# Boom_Deployment.net
KiCad netlist of a schematic drawn in Altium Designer
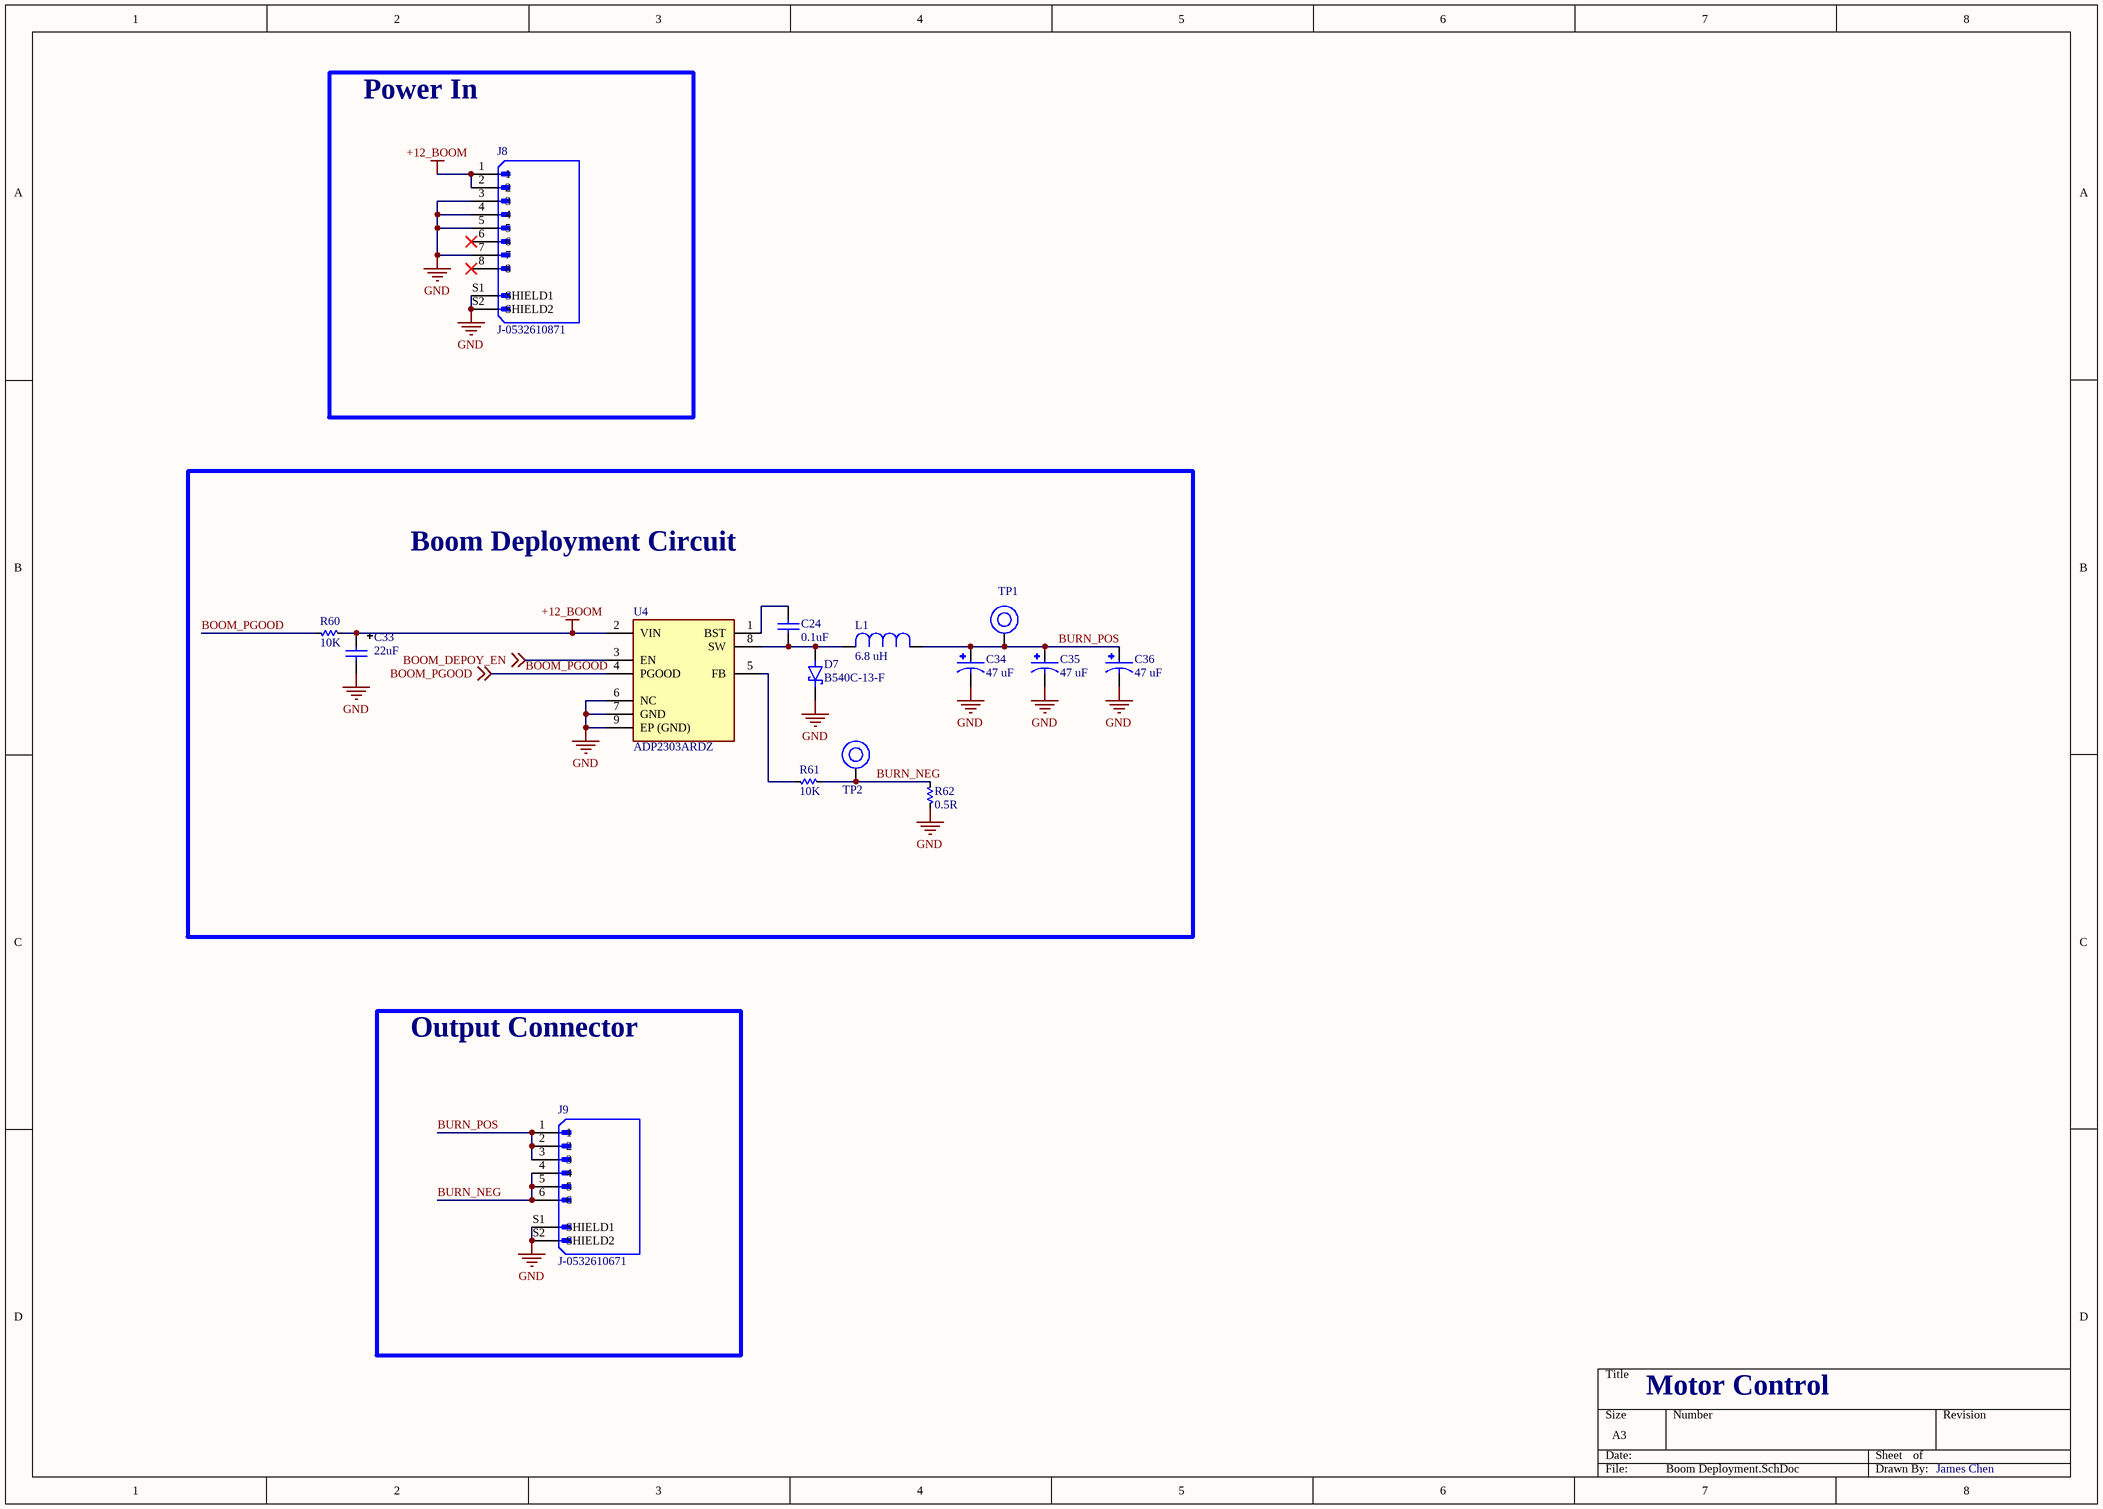
[diagram p0: Boom Deployment.SchDoc]

(export (version "E")
  (design (tool "Eeschema 10.0.6"))
  (components
    (comp (ref "C24")
      (value "0.1uF")
      (footprint "0603")
      (description "0.1 µF ±10% 25V Ceramic Capacitor X7R 0603 (1608 Metric)")
      (fields
        (field (name "DISTRIBUTOR PART #") "1276-1006-1-ND")
        (field (name "MANUFACTURER") "Samsung Electro-Mechanics")
      )
      (libsource (lib "Burn Wire Dev Board") (part "CC-104-K-25V-X7R-0603"))
    )
    (comp (ref "C33")
      (value "22uF")
      (footprint "CAP TANT 1206 (A) TCJ")
      (description "CAP TANT 22UF 10% 10V 1206")
      (fields
        (field (name "DISTRIBUTOR PART #") "478-11193-1-ND")
        (field (name "MANUFACTURER") "KYOCERA AVX")
      )
      (libsource (lib "Burn Wire Dev Board") (part "CT-225-M-20V-OTH-1206"))
    )
    (comp (ref "C34")
      (value "47 uF")
      (footprint "CC-25SVPF47M")
      (description "CAP ALUM POLY 47UF 20% 25V SMD")
      (fields
        (field (name "DISTRIBUTOR PART #") "P16513CT-ND")
        (field (name "MANUFACTURER") "Panasonic Electronic Components")
      )
      (libsource (lib "Burn Wire Dev Board") (part "CC-25SVPF47M"))
    )
    (comp (ref "C35")
      (value "47 uF")
      (footprint "CC-25SVPF47M")
      (description "CAP ALUM POLY 47UF 20% 25V SMD")
      (fields
        (field (name "DISTRIBUTOR PART #") "P16513CT-ND")
        (field (name "MANUFACTURER") "Panasonic Electronic Components")
      )
      (libsource (lib "Burn Wire Dev Board") (part "CC-25SVPF47M"))
    )
    (comp (ref "C36")
      (value "47 uF")
      (footprint "CC-25SVPF47M")
      (description "CAP ALUM POLY 47UF 20% 25V SMD")
      (fields
        (field (name "DISTRIBUTOR PART #") "P16513CT-ND")
        (field (name "MANUFACTURER") "Panasonic Electronic Components")
      )
      (libsource (lib "Burn Wire Dev Board") (part "CC-25SVPF47M"))
    )
    (comp (ref "D7")
      (value "B540C-13-F")
      (footprint "D-B540C-13-F")
      (description "DIODE SCHOTTKY 40V 5A SMC")
      (fields
        (field (name "MANUFACTURER") "Diodes Incorporated")
        (field (name "DISTRIBUTOR PART #") "B540C-FDICT-ND")
      )
      (libsource (lib "Burn Wire Dev Board") (part "D-B540C-13-F"))
    )
    (comp (ref "J8")
      (value "J-0532610871")
      (footprint "J-532610871")
      (description "CONN HEADER SMD R/A 8POS 1.25MM")
      (fields
        (field (name "MANFACTURER PART #") "0532610871")
        (field (name "DISTRIBUTOR PART #") "WM7626CT-ND")
      )
      (libsource (lib "OBC Development Board") (part "J-0532610871"))
    )
    (comp (ref "J9")
      (value "J-0532610671")
      (footprint "J-0532610671")
      (description "CONN HEADER SMD R/A 6POS 1.25MM")
      (fields
        (field (name "MANFACTURER PART #") "0532610671")
        (field (name "DISTRIBUTOR PART #") "WM7624CT-ND")
      )
      (libsource (lib "Burn Wire Dev Board") (part "J-0532610671"))
    )
    (comp (ref "L1")
      (value "6.8 uH")
      (footprint "L-IHLP4040DZER6R8M01")
      (description "FIXED IND 6.8UH 8A 23.3 MOHM SMD")
      (fields
        (field (name "MANUFACTURER") "Vishay Dale")
        (field (name "MANUFACTURER PART #") "IHLP4040DZER6R8M01")
      )
      (libsource (lib "Burn Wire Dev Board") (part "L-IHLP4040DZER6R8M01"))
    )
    (comp (ref "R60")
      (value "10K")
      (footprint "0603")
      (description "RES 10K OHM 1% 1/8W 0603")
      (fields
        (field (name "DISTRIBUTOR PART #") "RNCP0603FTD10K0CT-ND")
        (field (name "MANUFACTURER") "Stackpole Electronics Inc")
      )
      (libsource (lib "Burn Wire Dev Board") (part "RT-10K0-F-1/16W-0603"))
    )
    (comp (ref "R61")
      (value "10K")
      (footprint "0603")
      (description "RES 10K OHM 1% 1/8W 0603")
      (fields
        (field (name "DISTRIBUTOR PART #") "RNCP0603FTD10K0CT-ND")
        (field (name "MANUFACTURER") "Stackpole Electronics Inc")
      )
      (libsource (lib "Burn Wire Dev Board") (part "RT-10K0-F-1/16W-0603"))
    )
    (comp (ref "R62")
      (value "0.5R")
      (footprint "2010")
      (description "RES 0.5 OHM 1% 1W 2010")
      (fields
        (field (name "DISTRIBUTOR PART #") "541-10112-1-ND")
        (field (name "MANUFACTURER") "Vishay Dale")
      )
      (libsource (lib "Burn Wire Dev Board") (part "RT-0.5R0-F-1W-2010"))
    )
    (comp (ref "TP1")
      (value "TP")
      (footprint "TP")
      (description "Test Point")
      (libsource (lib "PowerManagmentBoard_V4.0") (part "TP"))
    )
    (comp (ref "TP2")
      (value "TP")
      (footprint "TP")
      (description "Test Point")
      (libsource (lib "PowerManagmentBoard_V4.0") (part "TP"))
    )
    (comp (ref "U4")
      (value "ADP2303ARDZ")
      (footprint "U-ADP2303ARDZ")
      (description "IC REG BUCK ADJUSTABLE 3A 8SOIC")
      (fields
        (field (name "MANUFACTURER") "Analog Devices Inc.")
        (field (name "DISTRIBUTOR PART #") "505-ADP2303ARDZ-ND")
      )
      (libsource (lib "Burn Wire Dev Board") (part "U-ADP2303ARDZ"))
    )
  )
  (nets
    (net (code "1") (name "+12_BOOM") (class "Default")
      (node (ref "C33") (pin "1") (pinfunction "1_1") (pintype "passive"))
      (node (ref "J8") (pin "1") (pinfunction "1_1") (pintype "passive"))
      (node (ref "J8") (pin "2") (pinfunction "2_2") (pintype "passive"))
      (node (ref "R60") (pin "2") (pintype "passive"))
      (node (ref "U4") (pin "2") (pinfunction "VIN_2") (pintype "passive"))
    )
    (net (code "3") (name "/BURN_NEG") (class "Default")
      (node (ref "J9") (pin "4") (pinfunction "4_4") (pintype "passive"))
      (node (ref "J9") (pin "5") (pinfunction "5_5") (pintype "passive"))
      (node (ref "J9") (pin "6") (pinfunction "6_6") (pintype "passive"))
      (node (ref "R61") (pin "2") (pintype "passive"))
      (node (ref "R62") (pin "2") (pintype "passive"))
      (node (ref "TP2") (pin "1") (pinfunction "1_1") (pintype "passive"))
    )
    (net (code "4") (name "/BURN_POS") (class "Default")
      (node (ref "C34") (pin "1") (pinfunction "1_1") (pintype "passive"))
      (node (ref "C35") (pin "1") (pinfunction "1_1") (pintype "passive"))
      (node (ref "C36") (pin "1") (pinfunction "1_1") (pintype "passive"))
      (node (ref "J9") (pin "1") (pinfunction "1_1") (pintype "passive"))
      (node (ref "J9") (pin "2") (pinfunction "2_2") (pintype "passive"))
      (node (ref "J9") (pin "3") (pinfunction "3_3") (pintype "passive"))
      (node (ref "L1") (pin "1") (pinfunction "1_1") (pintype "passive"))
      (node (ref "TP1") (pin "1") (pinfunction "1_1") (pintype "passive"))
    )
    (net (code "5") (name "BOOM_DEPOY_EN") (class "Default")
      (node (ref "U4") (pin "3") (pinfunction "EN_3") (pintype "passive"))
    )
    (net (code "6") (name "BOOM_PGOOD") (class "Default")
      (node (ref "R60") (pin "1") (pintype "passive"))
      (node (ref "U4") (pin "4") (pinfunction "PGOOD_4") (pintype "passive"))
    )
    (net (code "7") (name "GND") (class "Default")
      (node (ref "C33") (pin "2") (pinfunction "2_2") (pintype "passive"))
      (node (ref "C34") (pin "2") (pinfunction "2_2") (pintype "passive"))
      (node (ref "C35") (pin "2") (pinfunction "2_2") (pintype "passive"))
      (node (ref "C36") (pin "2") (pinfunction "2_2") (pintype "passive"))
      (node (ref "D7") (pin "C") (pinfunction "K_C") (pintype "passive"))
      (node (ref "J8") (pin "3") (pinfunction "3_3") (pintype "passive"))
      (node (ref "J8") (pin "4") (pinfunction "4_4") (pintype "passive"))
      (node (ref "J8") (pin "5") (pinfunction "5_5") (pintype "passive"))
      (node (ref "J8") (pin "7") (pinfunction "7_7") (pintype "passive"))
      (node (ref "J8") (pin "S1") (pinfunction "SHIELD1_S1") (pintype "passive"))
      (node (ref "J8") (pin "S2") (pinfunction "SHIELD2_S2") (pintype "passive"))
      (node (ref "J9") (pin "S1") (pinfunction "SHIELD1_S1") (pintype "passive"))
      (node (ref "J9") (pin "S2") (pinfunction "SHIELD2_S2") (pintype "passive"))
      (node (ref "R62") (pin "1") (pintype "passive"))
      (node (ref "U4") (pin "6") (pinfunction "NC_6") (pintype "passive"))
      (node (ref "U4") (pin "7") (pinfunction "GND_7") (pintype "passive"))
      (node (ref "U4") (pin "9") (pinfunction "EP_(GND)_9") (pintype "passive"))
    )
    (net (code "8") (name "Net-(U4-BST)") (class "Default")
      (node (ref "C24") (pin "2") (pinfunction "2_2") (pintype "passive"))
      (node (ref "U4") (pin "1") (pinfunction "BST_1") (pintype "passive"))
    )
    (net (code "9") (name "Net-(U4-FB)") (class "Default")
      (node (ref "R61") (pin "1") (pintype "passive"))
      (node (ref "U4") (pin "5") (pinfunction "FB_5") (pintype "passive"))
    )
    (net (code "10") (name "Net-(U4-SW)") (class "Default")
      (node (ref "C24") (pin "1") (pinfunction "1_1") (pintype "passive"))
      (node (ref "D7") (pin "A") (pinfunction "A_A") (pintype "passive"))
      (node (ref "L1") (pin "2") (pinfunction "2_2") (pintype "passive"))
      (node (ref "U4") (pin "8") (pinfunction "SW_8") (pintype "passive"))
    )
    (net (code "11") (name "unconnected-(J8-Pad6)") (class "Default")
      (node (ref "J8") (pin "6") (pinfunction "6_6") (pintype "passive+no_connect"))
    )
    (net (code "12") (name "unconnected-(J8-Pad8)") (class "Default")
      (node (ref "J8") (pin "8") (pinfunction "8_8") (pintype "passive+no_connect"))
    )
  )
)
